# 08_-_FTDI.net
KiCad netlist of a schematic drawn in Altium Designer
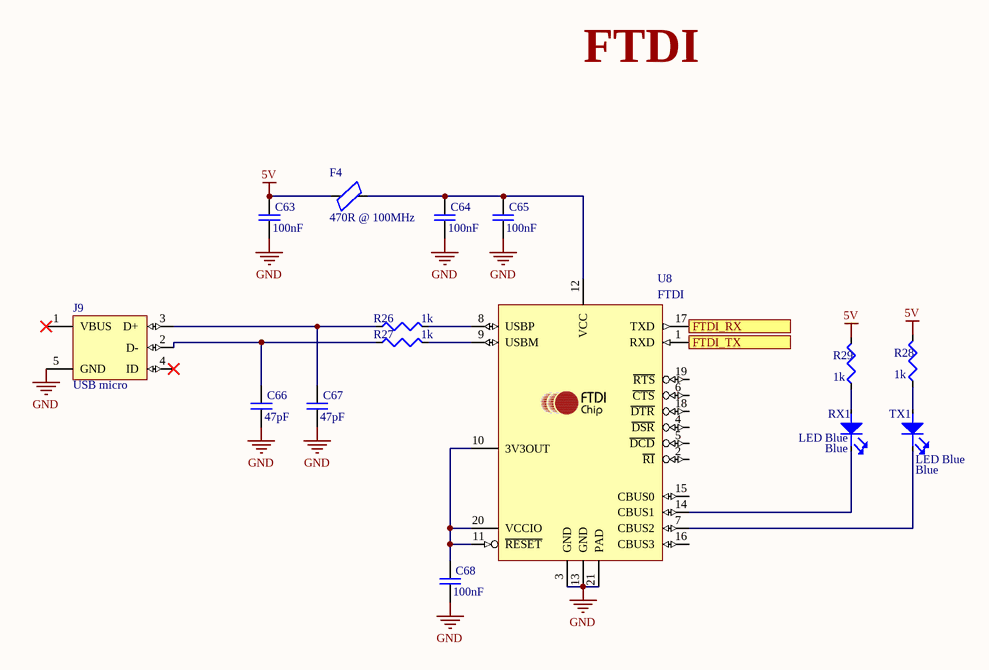
[diagram p0: [08] - FTDI.SchDoc]

(export (version "E")
  (design (tool "Eeschema 10.0.6"))
  (components
    (comp (ref "C63")
      (value "100nF")
      (footprint "C0603")
      (description "C0603")
      (fields (field (name "Comment") "02016D104KAT2A"))
      (libsource (lib "Passive components") (part "02016D104KAT2A"))
    )
    (comp (ref "C64")
      (value "100nF")
      (footprint "C0603")
      (description "C0603")
      (fields (field (name "Comment") "02016D104KAT2A"))
      (libsource (lib "Passive components") (part "02016D104KAT2A"))
    )
    (comp (ref "C65")
      (value "100nF")
      (footprint "C0603")
      (description "C0603")
      (fields (field (name "Comment") "02016D104KAT2A"))
      (libsource (lib "Passive components") (part "02016D104KAT2A"))
    )
    (comp (ref "C66")
      (value "47pF")
      (footprint "C0603")
      (description "C0603")
      (fields (field (name "Comment") "02016D104KAT2A"))
      (libsource (lib "Passive components") (part "02016D104KAT2A"))
    )
    (comp (ref "C67")
      (value "47pF")
      (footprint "C0603")
      (description "C0603")
      (fields (field (name "Comment") "02016D104KAT2A"))
      (libsource (lib "Passive components") (part "02016D104KAT2A"))
    )
    (comp (ref "C68")
      (value "100nF")
      (footprint "C0603")
      (description "C0603")
      (fields (field (name "Comment") "02016D104KAT2A"))
      (libsource (lib "Passive components") (part "02016D104KAT2A"))
    )
    (comp (ref "F4")
      (value "470R @ 100MHz")
      (footprint "Ferrite bead 0603")
      (description "Ferrite bead 0603")
      (fields (field (name "Comment") "BLM18AG121SN1D"))
      (libsource (lib "Passive components") (part "BLM18AG121SN1D"))
    )
    (comp (ref "J9")
      (value "USB micro")
      (footprint "USB micro")
      (libsource (lib "Connectors") (part "47590-0001"))
    )
    (comp (ref "R26")
      (value "1k")
      (footprint "R0603")
      (description "R0603")
      (fields (field (name "Comment") "CPF-A-0603B100KE1"))
      (libsource (lib "Passive components") (part "CPF-A-0603B100KE1"))
    )
    (comp (ref "R27")
      (value "1k")
      (footprint "R0603")
      (description "R0603")
      (fields (field (name "Comment") "CPF-A-0603B100KE1"))
      (libsource (lib "Passive components") (part "CPF-A-0603B100KE1"))
    )
    (comp (ref "R28")
      (value "1k")
      (footprint "R0603")
      (description "R0603")
      (fields (field (name "Comment") "CPF-A-0603B100KE1"))
      (libsource (lib "Passive components") (part "CPF-A-0603B100KE1"))
    )
    (comp (ref "R29")
      (value "1k")
      (footprint "R0603")
      (description "R0603")
      (fields (field (name "Comment") "CPF-A-0603B100KE1"))
      (libsource (lib "Passive components") (part "CPF-A-0603B100KE1"))
    )
    (comp (ref "RX1")
      (value "LED Blue")
      (footprint "L0603 BLUE")
      (description "LED 0603 Blue")
      (fields (field (name "COLOR") "Blue"))
      (libsource (lib "Diodes") (part "HSMG-C199"))
    )
    (comp (ref "TX1")
      (value "LED Blue")
      (footprint "L0603 BLUE")
      (description "LED 0603 Blue")
      (fields (field (name "COLOR") "Blue"))
      (libsource (lib "Diodes") (part "HSMG-C199"))
    )
    (comp (ref "U8")
      (value "FTDI")
      (footprint "FT231XQ-R")
      (description "USB to RS-232 converter")
      (libsource (lib "IC") (part "FT231XQ-R"))
    )
  )
  (nets
    (net (code "1") (name "/FTDI_RX") (class "Default")
      (node (ref "U8") (pin "17") (pinfunction "TXD_17") (pintype "output"))
    )
    (net (code "2") (name "/FTDI_TX") (class "Default")
      (node (ref "U8") (pin "1") (pinfunction "RXD_1") (pintype "input"))
    )
    (net (code "3") (name "5V") (class "Default")
      (node (ref "C63") (pin "2") (pinfunction "2_2") (pintype "passive"))
      (node (ref "F4") (pin "1") (pinfunction "1_1") (pintype "passive"))
      (node (ref "R28") (pin "2") (pinfunction "2_2") (pintype "passive"))
      (node (ref "R29") (pin "2") (pinfunction "2_2") (pintype "passive"))
    )
    (net (code "4") (name "GND") (class "Default")
      (node (ref "C63") (pin "1") (pinfunction "1_1") (pintype "passive"))
      (node (ref "C64") (pin "1") (pinfunction "1_1") (pintype "passive"))
      (node (ref "C65") (pin "1") (pinfunction "1_1") (pintype "passive"))
      (node (ref "C66") (pin "1") (pinfunction "1_1") (pintype "passive"))
      (node (ref "C67") (pin "1") (pinfunction "1_1") (pintype "passive"))
      (node (ref "C68") (pin "1") (pinfunction "1_1") (pintype "passive"))
      (node (ref "J9") (pin "5") (pinfunction "GND_5") (pintype "passive"))
      (node (ref "U8") (pin "13") (pinfunction "GND_13") (pintype "power_in"))
      (node (ref "U8") (pin "21") (pinfunction "PAD_21") (pintype "power_in"))
      (node (ref "U8") (pin "3") (pinfunction "GND_3") (pintype "power_in"))
    )
    (net (code "5") (name "Net-(J9-D+)") (class "Default")
      (node (ref "C67") (pin "2") (pinfunction "2_2") (pintype "passive"))
      (node (ref "J9") (pin "3") (pinfunction "D+_3") (pintype "bidirectional"))
      (node (ref "R26") (pin "1") (pinfunction "1_1") (pintype "passive"))
    )
    (net (code "6") (name "Net-(J9-D-)") (class "Default")
      (node (ref "C66") (pin "2") (pinfunction "2_2") (pintype "passive"))
      (node (ref "J9") (pin "2") (pinfunction "D-_2") (pintype "bidirectional"))
      (node (ref "R27") (pin "1") (pinfunction "1_1") (pintype "passive"))
    )
    (net (code "7") (name "Net-(R28-Pad1)") (class "Default")
      (node (ref "R28") (pin "1") (pinfunction "1_1") (pintype "passive"))
      (node (ref "TX1") (pin "1") (pinfunction "1_1") (pintype "passive"))
    )
    (net (code "8") (name "Net-(R29-Pad1)") (class "Default")
      (node (ref "R29") (pin "1") (pinfunction "1_1") (pintype "passive"))
      (node (ref "RX1") (pin "1") (pinfunction "1_1") (pintype "passive"))
    )
    (net (code "9") (name "Net-(U8-3V3OUT)") (class "Default")
      (node (ref "C68") (pin "2") (pinfunction "2_2") (pintype "passive"))
      (node (ref "U8") (pin "10") (pinfunction "3V3OUT_10") (pintype "power_in"))
      (node (ref "U8") (pin "11") (pinfunction "~{RESET}_11") (pintype "input"))
      (node (ref "U8") (pin "20") (pinfunction "VCCIO_20") (pintype "power_in"))
    )
    (net (code "10") (name "Net-(U8-CBUS1)") (class "Default")
      (node (ref "RX1") (pin "2") (pinfunction "2_2") (pintype "passive"))
      (node (ref "U8") (pin "14") (pinfunction "CBUS1_14") (pintype "bidirectional"))
    )
    (net (code "11") (name "Net-(U8-CBUS2)") (class "Default")
      (node (ref "TX1") (pin "2") (pinfunction "2_2") (pintype "passive"))
      (node (ref "U8") (pin "7") (pinfunction "CBUS2_7") (pintype "bidirectional"))
    )
    (net (code "12") (name "Net-(U8-USBM)") (class "Default")
      (node (ref "R27") (pin "2") (pinfunction "2_2") (pintype "passive"))
      (node (ref "U8") (pin "9") (pinfunction "USBM_9") (pintype "bidirectional"))
    )
    (net (code "13") (name "Net-(U8-USBP)") (class "Default")
      (node (ref "R26") (pin "2") (pinfunction "2_2") (pintype "passive"))
      (node (ref "U8") (pin "8") (pinfunction "USBP_8") (pintype "bidirectional"))
    )
    (net (code "14") (name "Net-(U8-VCC)") (class "Default")
      (node (ref "C64") (pin "2") (pinfunction "2_2") (pintype "passive"))
      (node (ref "C65") (pin "2") (pinfunction "2_2") (pintype "passive"))
      (node (ref "F4") (pin "2") (pinfunction "2_2") (pintype "passive"))
      (node (ref "U8") (pin "12") (pinfunction "VCC_12") (pintype "power_in"))
    )
    (net (code "15") (name "unconnected-(J9-ID-Pad4)") (class "Default")
      (node (ref "J9") (pin "4") (pinfunction "ID_4") (pintype "bidirectional+no_connect"))
    )
    (net (code "16") (name "unconnected-(J9-VBUS-Pad1)") (class "Default")
      (node (ref "J9") (pin "1") (pinfunction "VBUS_1") (pintype "passive+no_connect"))
    )
    (net (code "17") (name "unconnected-(U8-CBUS0-Pad15)") (class "Default")
      (node (ref "U8") (pin "15") (pinfunction "CBUS0_15") (pintype "bidirectional"))
    )
    (net (code "18") (name "unconnected-(U8-CBUS3-Pad16)") (class "Default")
      (node (ref "U8") (pin "16") (pinfunction "CBUS3_16") (pintype "bidirectional"))
    )
    (net (code "19") (name "unconnected-(U8-~{CTS}-Pad6)") (class "Default")
      (node (ref "U8") (pin "6") (pinfunction "~{CTS}_6") (pintype "bidirectional"))
    )
    (net (code "20") (name "unconnected-(U8-~{DCD}-Pad5)") (class "Default")
      (node (ref "U8") (pin "5") (pinfunction "~{DCD}_5") (pintype "bidirectional"))
    )
    (net (code "21") (name "unconnected-(U8-~{DSR}-Pad4)") (class "Default")
      (node (ref "U8") (pin "4") (pinfunction "~{DSR}_4") (pintype "bidirectional"))
    )
    (net (code "22") (name "unconnected-(U8-~{DTR}-Pad18)") (class "Default")
      (node (ref "U8") (pin "18") (pinfunction "~{DTR}_18") (pintype "bidirectional"))
    )
    (net (code "23") (name "unconnected-(U8-~{RI}-Pad2)") (class "Default")
      (node (ref "U8") (pin "2") (pinfunction "~{RI}_2") (pintype "bidirectional"))
    )
    (net (code "24") (name "unconnected-(U8-~{RTS}-Pad19)") (class "Default")
      (node (ref "U8") (pin "19") (pinfunction "~{RTS}_19") (pintype "bidirectional"))
    )
  )
)
